# AD_3.net
KiCad netlist of a schematic drawn in Altium Designer
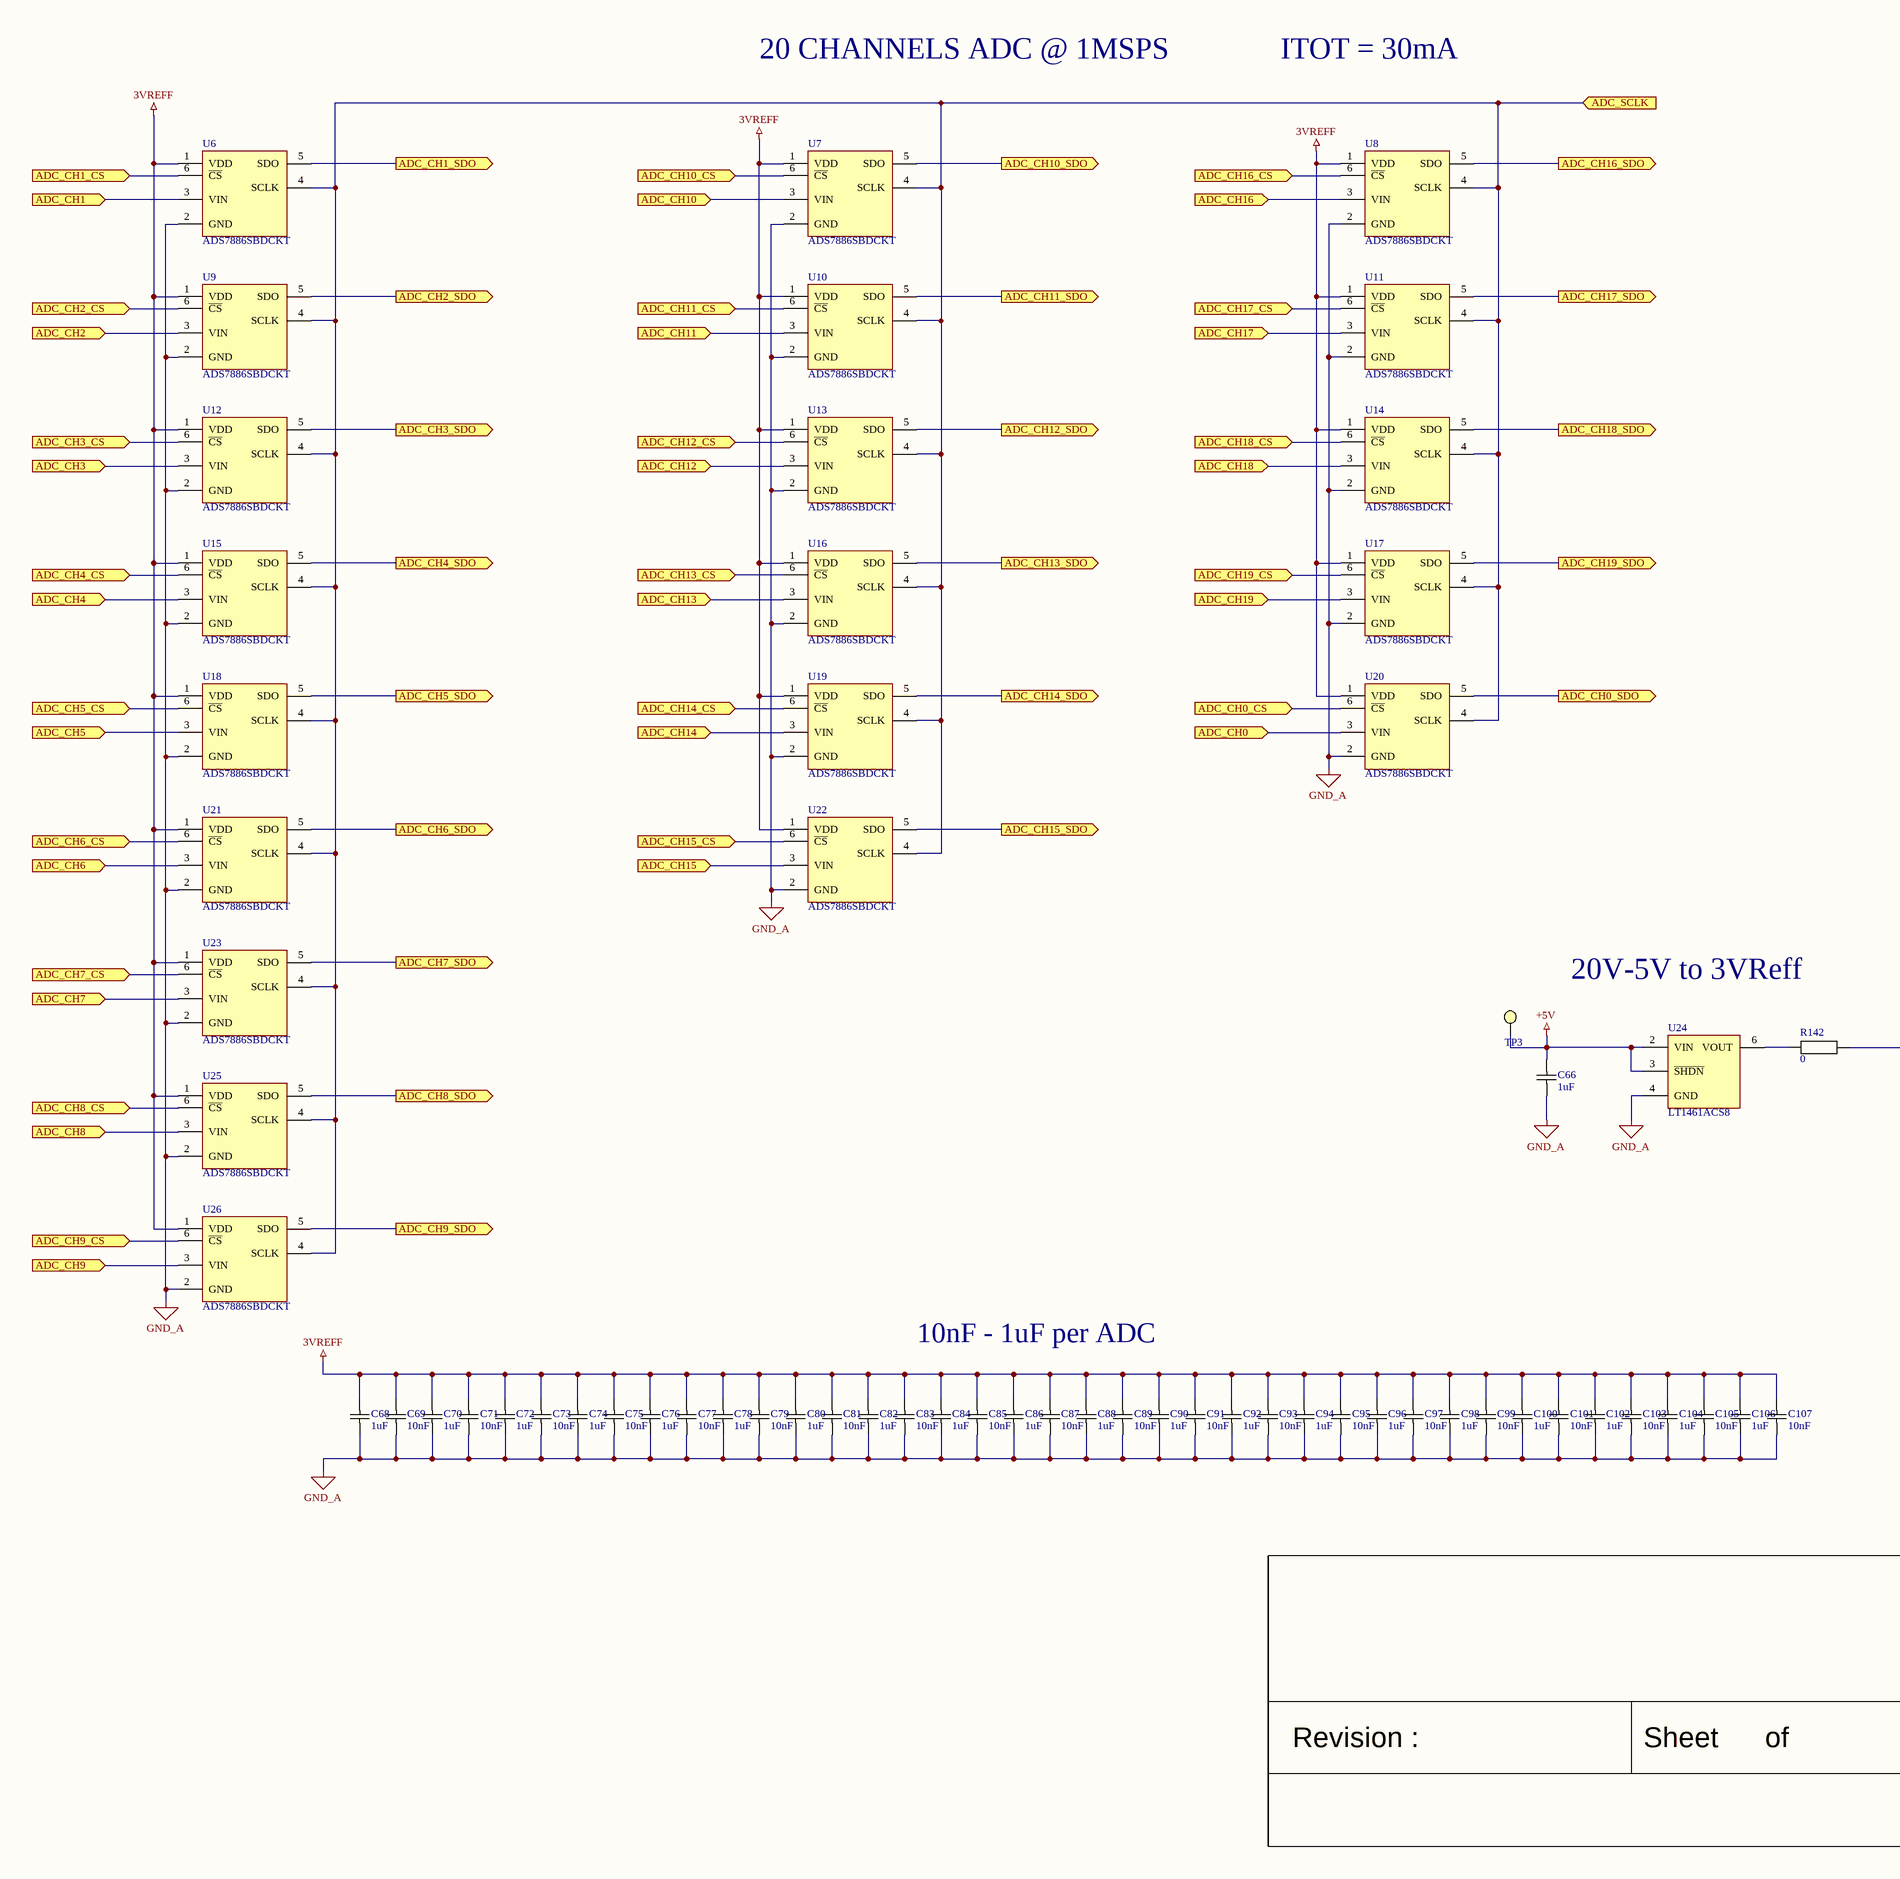
[diagram p0: AD_3.SchDoc, left]
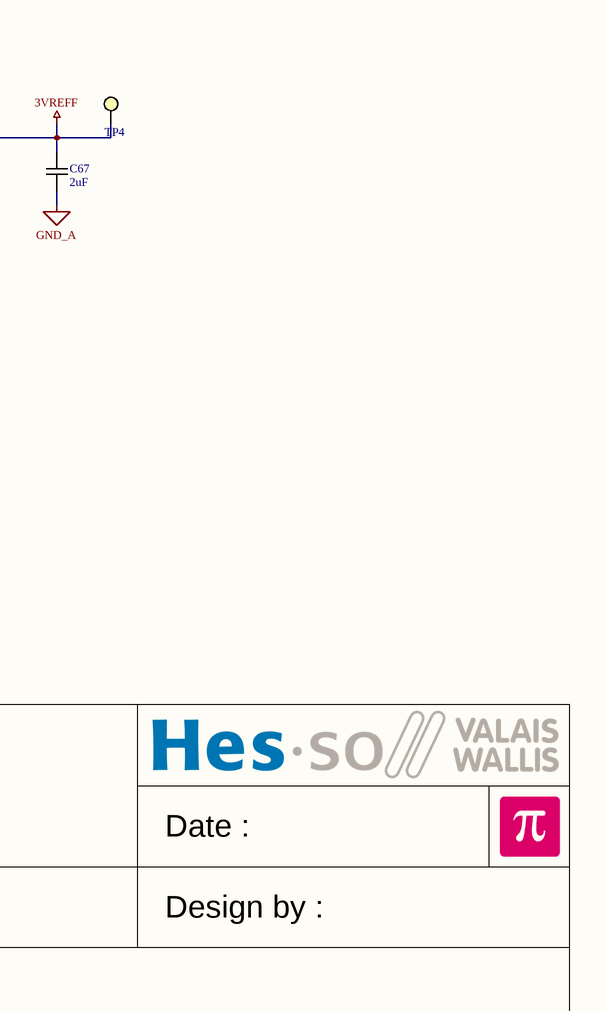
[diagram p1: AD_3.SchDoc, right]

(export (version "E")
  (design (tool "Eeschema 10.0.6"))
  (components
    (comp (ref "C66")
      (value "1uF")
      (footprint "CAPACITOR 1608 REFLOW")
      (description "Capacitor")
      (libsource (lib "Capacitor") (part "Capacitor"))
    )
    (comp (ref "C67")
      (value "2uF")
      (footprint "CAPACITOR 1608 REFLOW")
      (description "Capacitor")
      (libsource (lib "Capacitor") (part "Capacitor"))
    )
    (comp (ref "C68")
      (value "1uF")
      (footprint "CAPACITOR 1608 REFLOW")
      (description "Capacitor")
      (libsource (lib "Capacitor") (part "Capacitor"))
    )
    (comp (ref "C69")
      (value "10nF")
      (footprint "CAPACITOR 1608 REFLOW")
      (description "Capacitor")
      (libsource (lib "Capacitor") (part "Capacitor"))
    )
    (comp (ref "C70")
      (value "1uF")
      (footprint "CAPACITOR 1608 REFLOW")
      (description "Capacitor")
      (libsource (lib "Capacitor") (part "Capacitor"))
    )
    (comp (ref "C71")
      (value "10nF")
      (footprint "CAPACITOR 1608 REFLOW")
      (description "Capacitor")
      (libsource (lib "Capacitor") (part "Capacitor"))
    )
    (comp (ref "C72")
      (value "1uF")
      (footprint "CAPACITOR 1608 REFLOW")
      (description "Capacitor")
      (libsource (lib "Capacitor") (part "Capacitor"))
    )
    (comp (ref "C73")
      (value "10nF")
      (footprint "CAPACITOR 1608 REFLOW")
      (description "Capacitor")
      (libsource (lib "Capacitor") (part "Capacitor"))
    )
    (comp (ref "C74")
      (value "1uF")
      (footprint "CAPACITOR 1608 REFLOW")
      (description "Capacitor")
      (libsource (lib "Capacitor") (part "Capacitor"))
    )
    (comp (ref "C75")
      (value "10nF")
      (footprint "CAPACITOR 1608 REFLOW")
      (description "Capacitor")
      (libsource (lib "Capacitor") (part "Capacitor"))
    )
    (comp (ref "C76")
      (value "1uF")
      (footprint "CAPACITOR 1608 REFLOW")
      (description "Capacitor")
      (libsource (lib "Capacitor") (part "Capacitor"))
    )
    (comp (ref "C77")
      (value "10nF")
      (footprint "CAPACITOR 1608 REFLOW")
      (description "Capacitor")
      (libsource (lib "Capacitor") (part "Capacitor"))
    )
    (comp (ref "C78")
      (value "1uF")
      (footprint "CAPACITOR 1608 REFLOW")
      (description "Capacitor")
      (libsource (lib "Capacitor") (part "Capacitor"))
    )
    (comp (ref "C79")
      (value "10nF")
      (footprint "CAPACITOR 1608 REFLOW")
      (description "Capacitor")
      (libsource (lib "Capacitor") (part "Capacitor"))
    )
    (comp (ref "C80")
      (value "1uF")
      (footprint "CAPACITOR 1608 REFLOW")
      (description "Capacitor")
      (libsource (lib "Capacitor") (part "Capacitor"))
    )
    (comp (ref "C81")
      (value "10nF")
      (footprint "CAPACITOR 1608 REFLOW")
      (description "Capacitor")
      (libsource (lib "Capacitor") (part "Capacitor"))
    )
    (comp (ref "C82")
      (value "1uF")
      (footprint "CAPACITOR 1608 REFLOW")
      (description "Capacitor")
      (libsource (lib "Capacitor") (part "Capacitor"))
    )
    (comp (ref "C83")
      (value "10nF")
      (footprint "CAPACITOR 1608 REFLOW")
      (description "Capacitor")
      (libsource (lib "Capacitor") (part "Capacitor"))
    )
    (comp (ref "C84")
      (value "1uF")
      (footprint "CAPACITOR 1608 REFLOW")
      (description "Capacitor")
      (libsource (lib "Capacitor") (part "Capacitor"))
    )
    (comp (ref "C85")
      (value "10nF")
      (footprint "CAPACITOR 1608 REFLOW")
      (description "Capacitor")
      (libsource (lib "Capacitor") (part "Capacitor"))
    )
    (comp (ref "C86")
      (value "1uF")
      (footprint "CAPACITOR 1608 REFLOW")
      (description "Capacitor")
      (libsource (lib "Capacitor") (part "Capacitor"))
    )
    (comp (ref "C87")
      (value "10nF")
      (footprint "CAPACITOR 1608 REFLOW")
      (description "Capacitor")
      (libsource (lib "Capacitor") (part "Capacitor"))
    )
    (comp (ref "C88")
      (value "1uF")
      (footprint "CAPACITOR 1608 REFLOW")
      (description "Capacitor")
      (libsource (lib "Capacitor") (part "Capacitor"))
    )
    (comp (ref "C89")
      (value "10nF")
      (footprint "CAPACITOR 1608 REFLOW")
      (description "Capacitor")
      (libsource (lib "Capacitor") (part "Capacitor"))
    )
    (comp (ref "C90")
      (value "1uF")
      (footprint "CAPACITOR 1608 REFLOW")
      (description "Capacitor")
      (libsource (lib "Capacitor") (part "Capacitor"))
    )
    (comp (ref "C91")
      (value "10nF")
      (footprint "CAPACITOR 1608 REFLOW")
      (description "Capacitor")
      (libsource (lib "Capacitor") (part "Capacitor"))
    )
    (comp (ref "C92")
      (value "1uF")
      (footprint "CAPACITOR 1608 REFLOW")
      (description "Capacitor")
      (libsource (lib "Capacitor") (part "Capacitor"))
    )
    (comp (ref "C93")
      (value "10nF")
      (footprint "CAPACITOR 1608 REFLOW")
      (description "Capacitor")
      (libsource (lib "Capacitor") (part "Capacitor"))
    )
    (comp (ref "C94")
      (value "1uF")
      (footprint "CAPACITOR 1608 REFLOW")
      (description "Capacitor")
      (libsource (lib "Capacitor") (part "Capacitor"))
    )
    (comp (ref "C95")
      (value "10nF")
      (footprint "CAPACITOR 1608 REFLOW")
      (description "Capacitor")
      (libsource (lib "Capacitor") (part "Capacitor"))
    )
    (comp (ref "C96")
      (value "1uF")
      (footprint "CAPACITOR 1608 REFLOW")
      (description "Capacitor")
      (libsource (lib "Capacitor") (part "Capacitor"))
    )
    (comp (ref "C97")
      (value "10nF")
      (footprint "CAPACITOR 1608 REFLOW")
      (description "Capacitor")
      (libsource (lib "Capacitor") (part "Capacitor"))
    )
    (comp (ref "C98")
      (value "1uF")
      (footprint "CAPACITOR 1608 REFLOW")
      (description "Capacitor")
      (libsource (lib "Capacitor") (part "Capacitor"))
    )
    (comp (ref "C99")
      (value "10nF")
      (footprint "CAPACITOR 1608 REFLOW")
      (description "Capacitor")
      (libsource (lib "Capacitor") (part "Capacitor"))
    )
    (comp (ref "C100")
      (value "1uF")
      (footprint "CAPACITOR 1608 REFLOW")
      (description "Capacitor")
      (libsource (lib "Capacitor") (part "Capacitor"))
    )
    (comp (ref "C101")
      (value "10nF")
      (footprint "CAPACITOR 1608 REFLOW")
      (description "Capacitor")
      (libsource (lib "Capacitor") (part "Capacitor"))
    )
    (comp (ref "C102")
      (value "1uF")
      (footprint "CAPACITOR 1608 REFLOW")
      (description "Capacitor")
      (libsource (lib "Capacitor") (part "Capacitor"))
    )
    (comp (ref "C103")
      (value "10nF")
      (footprint "CAPACITOR 1608 REFLOW")
      (description "Capacitor")
      (libsource (lib "Capacitor") (part "Capacitor"))
    )
    (comp (ref "C104")
      (value "1uF")
      (footprint "CAPACITOR 1608 REFLOW")
      (description "Capacitor")
      (libsource (lib "Capacitor") (part "Capacitor"))
    )
    (comp (ref "C105")
      (value "10nF")
      (footprint "CAPACITOR 1608 REFLOW")
      (description "Capacitor")
      (libsource (lib "Capacitor") (part "Capacitor"))
    )
    (comp (ref "C106")
      (value "1uF")
      (footprint "CAPACITOR 1608 REFLOW")
      (description "Capacitor")
      (libsource (lib "Capacitor") (part "Capacitor"))
    )
    (comp (ref "C107")
      (value "10nF")
      (footprint "CAPACITOR 1608 REFLOW")
      (description "Capacitor")
      (libsource (lib "Capacitor") (part "Capacitor"))
    )
    (comp (ref "R142")
      (value "0")
      (footprint "RESISTOR 1608 REFLOW")
      (description "Resistor 1% 50V 100mW 1608(0603)")
      (libsource (lib "Resistor") (part "Resistor"))
    )
    (comp (ref "TP3")
      (value "*")
      (footprint "Test Point Keystone Miniature RED")
      (description "Test Point")
      (libsource (lib "Testpoint") (part "Test Point"))
    )
    (comp (ref "TP4")
      (value "*")
      (footprint "Test Point Keystone Miniature RED")
      (description "Test Point")
      (libsource (lib "Testpoint") (part "Test Point"))
    )
    (comp (ref "U6")
      (value "ADS7886SBDCKT")
      (footprint "SOT23-6 P0.95 C1.5x3.0 H1.3")
      (description "12-Bit, 1-MSPS, Micro-Power, Miniature SAR Analog-to-Digital Converters")
      (libsource (lib "Converter") (part "ADS7886SBDCKT"))
    )
    (comp (ref "U7")
      (value "ADS7886SBDCKT")
      (footprint "SOT23-6 P0.95 C1.5x3.0 H1.3")
      (description "12-Bit, 1-MSPS, Micro-Power, Miniature SAR Analog-to-Digital Converters")
      (libsource (lib "Converter") (part "ADS7886SBDCKT"))
    )
    (comp (ref "U8")
      (value "ADS7886SBDCKT")
      (footprint "SOT23-6 P0.95 C1.5x3.0 H1.3")
      (description "12-Bit, 1-MSPS, Micro-Power, Miniature SAR Analog-to-Digital Converters")
      (libsource (lib "Converter") (part "ADS7886SBDCKT"))
    )
    (comp (ref "U9")
      (value "ADS7886SBDCKT")
      (footprint "SOT23-6 P0.95 C1.5x3.0 H1.3")
      (description "12-Bit, 1-MSPS, Micro-Power, Miniature SAR Analog-to-Digital Converters")
      (libsource (lib "Converter") (part "ADS7886SBDCKT"))
    )
    (comp (ref "U10")
      (value "ADS7886SBDCKT")
      (footprint "SOT23-6 P0.95 C1.5x3.0 H1.3")
      (description "12-Bit, 1-MSPS, Micro-Power, Miniature SAR Analog-to-Digital Converters")
      (libsource (lib "Converter") (part "ADS7886SBDCKT"))
    )
    (comp (ref "U11")
      (value "ADS7886SBDCKT")
      (footprint "SOT23-6 P0.95 C1.5x3.0 H1.3")
      (description "12-Bit, 1-MSPS, Micro-Power, Miniature SAR Analog-to-Digital Converters")
      (libsource (lib "Converter") (part "ADS7886SBDCKT"))
    )
    (comp (ref "U12")
      (value "ADS7886SBDCKT")
      (footprint "SOT23-6 P0.95 C1.5x3.0 H1.3")
      (description "12-Bit, 1-MSPS, Micro-Power, Miniature SAR Analog-to-Digital Converters")
      (libsource (lib "Converter") (part "ADS7886SBDCKT"))
    )
    (comp (ref "U13")
      (value "ADS7886SBDCKT")
      (footprint "SOT23-6 P0.95 C1.5x3.0 H1.3")
      (description "12-Bit, 1-MSPS, Micro-Power, Miniature SAR Analog-to-Digital Converters")
      (libsource (lib "Converter") (part "ADS7886SBDCKT"))
    )
    (comp (ref "U14")
      (value "ADS7886SBDCKT")
      (footprint "SOT23-6 P0.95 C1.5x3.0 H1.3")
      (description "12-Bit, 1-MSPS, Micro-Power, Miniature SAR Analog-to-Digital Converters")
      (libsource (lib "Converter") (part "ADS7886SBDCKT"))
    )
    (comp (ref "U15")
      (value "ADS7886SBDCKT")
      (footprint "SOT23-6 P0.95 C1.5x3.0 H1.3")
      (description "12-Bit, 1-MSPS, Micro-Power, Miniature SAR Analog-to-Digital Converters")
      (libsource (lib "Converter") (part "ADS7886SBDCKT"))
    )
    (comp (ref "U16")
      (value "ADS7886SBDCKT")
      (footprint "SOT23-6 P0.95 C1.5x3.0 H1.3")
      (description "12-Bit, 1-MSPS, Micro-Power, Miniature SAR Analog-to-Digital Converters")
      (libsource (lib "Converter") (part "ADS7886SBDCKT"))
    )
    (comp (ref "U17")
      (value "ADS7886SBDCKT")
      (footprint "SOT23-6 P0.95 C1.5x3.0 H1.3")
      (description "12-Bit, 1-MSPS, Micro-Power, Miniature SAR Analog-to-Digital Converters")
      (libsource (lib "Converter") (part "ADS7886SBDCKT"))
    )
    (comp (ref "U18")
      (value "ADS7886SBDCKT")
      (footprint "SOT23-6 P0.95 C1.5x3.0 H1.3")
      (description "12-Bit, 1-MSPS, Micro-Power, Miniature SAR Analog-to-Digital Converters")
      (libsource (lib "Converter") (part "ADS7886SBDCKT"))
    )
    (comp (ref "U19")
      (value "ADS7886SBDCKT")
      (footprint "SOT23-6 P0.95 C1.5x3.0 H1.3")
      (description "12-Bit, 1-MSPS, Micro-Power, Miniature SAR Analog-to-Digital Converters")
      (libsource (lib "Converter") (part "ADS7886SBDCKT"))
    )
    (comp (ref "U20")
      (value "ADS7886SBDCKT")
      (footprint "SOT23-6 P0.95 C1.5x3.0 H1.3")
      (description "12-Bit, 1-MSPS, Micro-Power, Miniature SAR Analog-to-Digital Converters")
      (libsource (lib "Converter") (part "ADS7886SBDCKT"))
    )
    (comp (ref "U21")
      (value "ADS7886SBDCKT")
      (footprint "SOT23-6 P0.95 C1.5x3.0 H1.3")
      (description "12-Bit, 1-MSPS, Micro-Power, Miniature SAR Analog-to-Digital Converters")
      (libsource (lib "Converter") (part "ADS7886SBDCKT"))
    )
    (comp (ref "U22")
      (value "ADS7886SBDCKT")
      (footprint "SOT23-6 P0.95 C1.5x3.0 H1.3")
      (description "12-Bit, 1-MSPS, Micro-Power, Miniature SAR Analog-to-Digital Converters")
      (libsource (lib "Converter") (part "ADS7886SBDCKT"))
    )
    (comp (ref "U23")
      (value "ADS7886SBDCKT")
      (footprint "SOT23-6 P0.95 C1.5x3.0 H1.3")
      (description "12-Bit, 1-MSPS, Micro-Power, Miniature SAR Analog-to-Digital Converters")
      (libsource (lib "Converter") (part "ADS7886SBDCKT"))
    )
    (comp (ref "U24")
      (value "LT1461ACS8")
      (footprint "SO8 P1.27 C4.0X5.0 H1.75")
      (description "Micropower Precision Low Dropout Series Voltage Reference Family")
      (libsource (lib "Regulator") (part "LT1461ACS8"))
    )
    (comp (ref "U25")
      (value "ADS7886SBDCKT")
      (footprint "SOT23-6 P0.95 C1.5x3.0 H1.3")
      (description "12-Bit, 1-MSPS, Micro-Power, Miniature SAR Analog-to-Digital Converters")
      (libsource (lib "Converter") (part "ADS7886SBDCKT"))
    )
    (comp (ref "U26")
      (value "ADS7886SBDCKT")
      (footprint "SOT23-6 P0.95 C1.5x3.0 H1.3")
      (description "12-Bit, 1-MSPS, Micro-Power, Miniature SAR Analog-to-Digital Converters")
      (libsource (lib "Converter") (part "ADS7886SBDCKT"))
    )
  )
  (nets
    (net (code "1") (name "+5V") (class "Default")
      (node (ref "C66") (pin "2") (pinfunction "2_2") (pintype "passive"))
      (node (ref "TP3") (pin "1") (pinfunction "1_1") (pintype "passive"))
      (node (ref "U24") (pin "2") (pinfunction "VIN_2") (pintype "passive"))
      (node (ref "U24") (pin "3") (pinfunction "~{SHDN}_3") (pintype "passive"))
    )
    (net (code "2") (name "/ADC_CH0") (class "Default")
      (node (ref "U20") (pin "3") (pinfunction "VIN_3") (pintype "passive"))
    )
    (net (code "3") (name "/ADC_CH0_CS") (class "Default")
      (node (ref "U20") (pin "6") (pinfunction "~{CS}_6") (pintype "passive"))
    )
    (net (code "4") (name "/ADC_CH0_SDO") (class "Default")
      (node (ref "U20") (pin "5") (pinfunction "SDO_5") (pintype "passive"))
    )
    (net (code "5") (name "/ADC_CH1") (class "Default")
      (node (ref "U6") (pin "3") (pinfunction "VIN_3") (pintype "passive"))
    )
    (net (code "6") (name "/ADC_CH1_CS") (class "Default")
      (node (ref "U6") (pin "6") (pinfunction "~{CS}_6") (pintype "passive"))
    )
    (net (code "7") (name "/ADC_CH1_SDO") (class "Default")
      (node (ref "U6") (pin "5") (pinfunction "SDO_5") (pintype "passive"))
    )
    (net (code "8") (name "/ADC_CH2") (class "Default")
      (node (ref "U9") (pin "3") (pinfunction "VIN_3") (pintype "passive"))
    )
    (net (code "9") (name "/ADC_CH2_CS") (class "Default")
      (node (ref "U9") (pin "6") (pinfunction "~{CS}_6") (pintype "passive"))
    )
    (net (code "10") (name "/ADC_CH2_SDO") (class "Default")
      (node (ref "U9") (pin "5") (pinfunction "SDO_5") (pintype "passive"))
    )
    (net (code "11") (name "/ADC_CH3") (class "Default")
      (node (ref "U12") (pin "3") (pinfunction "VIN_3") (pintype "passive"))
    )
    (net (code "12") (name "/ADC_CH3_CS") (class "Default")
      (node (ref "U12") (pin "6") (pinfunction "~{CS}_6") (pintype "passive"))
    )
    (net (code "13") (name "/ADC_CH3_SDO") (class "Default")
      (node (ref "U12") (pin "5") (pinfunction "SDO_5") (pintype "passive"))
    )
    (net (code "14") (name "/ADC_CH4") (class "Default")
      (node (ref "U15") (pin "3") (pinfunction "VIN_3") (pintype "passive"))
    )
    (net (code "15") (name "/ADC_CH4_CS") (class "Default")
      (node (ref "U15") (pin "6") (pinfunction "~{CS}_6") (pintype "passive"))
    )
    (net (code "16") (name "/ADC_CH4_SDO") (class "Default")
      (node (ref "U15") (pin "5") (pinfunction "SDO_5") (pintype "passive"))
    )
    (net (code "17") (name "/ADC_CH5") (class "Default")
      (node (ref "U18") (pin "3") (pinfunction "VIN_3") (pintype "passive"))
    )
    (net (code "18") (name "/ADC_CH5_CS") (class "Default")
      (node (ref "U18") (pin "6") (pinfunction "~{CS}_6") (pintype "passive"))
    )
    (net (code "19") (name "/ADC_CH5_SDO") (class "Default")
      (node (ref "U18") (pin "5") (pinfunction "SDO_5") (pintype "passive"))
    )
    (net (code "20") (name "/ADC_CH6") (class "Default")
      (node (ref "U21") (pin "3") (pinfunction "VIN_3") (pintype "passive"))
    )
    (net (code "21") (name "/ADC_CH6_CS") (class "Default")
      (node (ref "U21") (pin "6") (pinfunction "~{CS}_6") (pintype "passive"))
    )
    (net (code "22") (name "/ADC_CH6_SDO") (class "Default")
      (node (ref "U21") (pin "5") (pinfunction "SDO_5") (pintype "passive"))
    )
    (net (code "23") (name "/ADC_CH7") (class "Default")
      (node (ref "U23") (pin "3") (pinfunction "VIN_3") (pintype "passive"))
    )
    (net (code "24") (name "/ADC_CH7_CS") (class "Default")
      (node (ref "U23") (pin "6") (pinfunction "~{CS}_6") (pintype "passive"))
    )
    (net (code "25") (name "/ADC_CH7_SDO") (class "Default")
      (node (ref "U23") (pin "5") (pinfunction "SDO_5") (pintype "passive"))
    )
    (net (code "26") (name "/ADC_CH8") (class "Default")
      (node (ref "U25") (pin "3") (pinfunction "VIN_3") (pintype "passive"))
    )
    (net (code "27") (name "/ADC_CH8_CS") (class "Default")
      (node (ref "U25") (pin "6") (pinfunction "~{CS}_6") (pintype "passive"))
    )
    (net (code "28") (name "/ADC_CH8_SDO") (class "Default")
      (node (ref "U25") (pin "5") (pinfunction "SDO_5") (pintype "passive"))
    )
    (net (code "29") (name "/ADC_CH9") (class "Default")
      (node (ref "U26") (pin "3") (pinfunction "VIN_3") (pintype "passive"))
    )
    (net (code "30") (name "/ADC_CH9_CS") (class "Default")
      (node (ref "U26") (pin "6") (pinfunction "~{CS}_6") (pintype "passive"))
    )
    (net (code "31") (name "/ADC_CH9_SDO") (class "Default")
      (node (ref "U26") (pin "5") (pinfunction "SDO_5") (pintype "passive"))
    )
    (net (code "32") (name "/ADC_CH10") (class "Default")
      (node (ref "U7") (pin "3") (pinfunction "VIN_3") (pintype "passive"))
    )
    (net (code "33") (name "/ADC_CH10_CS") (class "Default")
      (node (ref "U7") (pin "6") (pinfunction "~{CS}_6") (pintype "passive"))
    )
    (net (code "34") (name "/ADC_CH10_SDO") (class "Default")
      (node (ref "U7") (pin "5") (pinfunction "SDO_5") (pintype "passive"))
    )
    (net (code "35") (name "/ADC_CH11") (class "Default")
      (node (ref "U10") (pin "3") (pinfunction "VIN_3") (pintype "passive"))
    )
    (net (code "36") (name "/ADC_CH11_CS") (class "Default")
      (node (ref "U10") (pin "6") (pinfunction "~{CS}_6") (pintype "passive"))
    )
    (net (code "37") (name "/ADC_CH11_SDO") (class "Default")
      (node (ref "U10") (pin "5") (pinfunction "SDO_5") (pintype "passive"))
    )
    (net (code "38") (name "/ADC_CH12") (class "Default")
      (node (ref "U13") (pin "3") (pinfunction "VIN_3") (pintype "passive"))
    )
    (net (code "39") (name "/ADC_CH12_CS") (class "Default")
      (node (ref "U13") (pin "6") (pinfunction "~{CS}_6") (pintype "passive"))
    )
    (net (code "40") (name "/ADC_CH12_SDO") (class "Default")
      (node (ref "U13") (pin "5") (pinfunction "SDO_5") (pintype "passive"))
    )
    (net (code "41") (name "/ADC_CH13") (class "Default")
      (node (ref "U16") (pin "3") (pinfunction "VIN_3") (pintype "passive"))
    )
    (net (code "42") (name "/ADC_CH13_CS") (class "Default")
      (node (ref "U16") (pin "6") (pinfunction "~{CS}_6") (pintype "passive"))
    )
    (net (code "43") (name "/ADC_CH13_SDO") (class "Default")
      (node (ref "U16") (pin "5") (pinfunction "SDO_5") (pintype "passive"))
    )
    (net (code "44") (name "/ADC_CH14") (class "Default")
      (node (ref "U19") (pin "3") (pinfunction "VIN_3") (pintype "passive"))
    )
    (net (code "45") (name "/ADC_CH14_CS") (class "Default")
      (node (ref "U19") (pin "6") (pinfunction "~{CS}_6") (pintype "passive"))
    )
    (net (code "46") (name "/ADC_CH14_SDO") (class "Default")
      (node (ref "U19") (pin "5") (pinfunction "SDO_5") (pintype "passive"))
    )
    (net (code "47") (name "/ADC_CH15") (class "Default")
      (node (ref "U22") (pin "3") (pinfunction "VIN_3") (pintype "passive"))
    )
    (net (code "48") (name "/ADC_CH15_CS") (class "Default")
      (node (ref "U22") (pin "6") (pinfunction "~{CS}_6") (pintype "passive"))
    )
    (net (code "49") (name "/ADC_CH15_SDO") (class "Default")
      (node (ref "U22") (pin "5") (pinfunction "SDO_5") (pintype "passive"))
    )
    (net (code "50") (name "/ADC_CH16") (class "Default")
      (node (ref "U8") (pin "3") (pinfunction "VIN_3") (pintype "passive"))
    )
    (net (code "51") (name "/ADC_CH16_CS") (class "Default")
      (node (ref "U8") (pin "6") (pinfunction "~{CS}_6") (pintype "passive"))
    )
    (net (code "52") (name "/ADC_CH16_SDO") (class "Default")
      (node (ref "U8") (pin "5") (pinfunction "SDO_5") (pintype "passive"))
    )
    (net (code "53") (name "/ADC_CH17") (class "Default")
      (node (ref "U11") (pin "3") (pinfunction "VIN_3") (pintype "passive"))
    )
    (net (code "54") (name "/ADC_CH17_CS") (class "Default")
      (node (ref "U11") (pin "6") (pinfunction "~{CS}_6") (pintype "passive"))
    )
    (net (code "55") (name "/ADC_CH17_SDO") (class "Default")
      (node (ref "U11") (pin "5") (pinfunction "SDO_5") (pintype "passive"))
    )
    (net (code "56") (name "/ADC_CH18") (class "Default")
      (node (ref "U14") (pin "3") (pinfunction "VIN_3") (pintype "passive"))
    )
    (net (code "57") (name "/ADC_CH18_CS") (class "Default")
      (node (ref "U14") (pin "6") (pinfunction "~{CS}_6") (pintype "passive"))
    )
    (net (code "58") (name "/ADC_CH18_SDO") (class "Default")
      (node (ref "U14") (pin "5") (pinfunction "SDO_5") (pintype "passive"))
    )
    (net (code "59") (name "/ADC_CH19") (class "Default")
      (node (ref "U17") (pin "3") (pinfunction "VIN_3") (pintype "passive"))
    )
    (net (code "60") (name "/ADC_CH19_CS") (class "Default")
      (node (ref "U17") (pin "6") (pinfunction "~{CS}_6") (pintype "passive"))
    )
    (net (code "61") (name "/ADC_CH19_SDO") (class "Default")
      (node (ref "U17") (pin "5") (pinfunction "SDO_5") (pintype "passive"))
    )
    (net (code "62") (name "/ADC_SCLK") (class "Default")
      (node (ref "U10") (pin "4") (pinfunction "SCLK_4") (pintype "passive"))
      (node (ref "U11") (pin "4") (pinfunction "SCLK_4") (pintype "passive"))
      (node (ref "U12") (pin "4") (pinfunction "SCLK_4") (pintype "passive"))
      (node (ref "U13") (pin "4") (pinfunction "SCLK_4") (pintype "passive"))
      (node (ref "U14") (pin "4") (pinfunction "SCLK_4") (pintype "passive"))
      (node (ref "U15") (pin "4") (pinfunction "SCLK_4") (pintype "passive"))
      (node (ref "U16") (pin "4") (pinfunction "SCLK_4") (pintype "passive"))
      (node (ref "U17") (pin "4") (pinfunction "SCLK_4") (pintype "passive"))
      (node (ref "U18") (pin "4") (pinfunction "SCLK_4") (pintype "passive"))
      (node (ref "U19") (pin "4") (pinfunction "SCLK_4") (pintype "passive"))
      (node (ref "U20") (pin "4") (pinfunction "SCLK_4") (pintype "passive"))
      (node (ref "U21") (pin "4") (pinfunction "SCLK_4") (pintype "passive"))
      (node (ref "U22") (pin "4") (pinfunction "SCLK_4") (pintype "passive"))
      (node (ref "U23") (pin "4") (pinfunction "SCLK_4") (pintype "passive"))
      (node (ref "U25") (pin "4") (pinfunction "SCLK_4") (pintype "passive"))
      (node (ref "U26") (pin "4") (pinfunction "SCLK_4") (pintype "passive"))
      (node (ref "U6") (pin "4") (pinfunction "SCLK_4") (pintype "passive"))
      (node (ref "U7") (pin "4") (pinfunction "SCLK_4") (pintype "passive"))
      (node (ref "U8") (pin "4") (pinfunction "SCLK_4") (pintype "passive"))
      (node (ref "U9") (pin "4") (pinfunction "SCLK_4") (pintype "passive"))
    )
    (net (code "63") (name "3VREFF") (class "Default")
      (node (ref "C100") (pin "2") (pinfunction "2_2") (pintype "passive"))
      (node (ref "C101") (pin "2") (pinfunction "2_2") (pintype "passive"))
      (node (ref "C102") (pin "2") (pinfunction "2_2") (pintype "passive"))
      (node (ref "C103") (pin "2") (pinfunction "2_2") (pintype "passive"))
      (node (ref "C104") (pin "2") (pinfunction "2_2") (pintype "passive"))
      (node (ref "C105") (pin "2") (pinfunction "2_2") (pintype "passive"))
      (node (ref "C106") (pin "2") (pinfunction "2_2") (pintype "passive"))
      (node (ref "C107") (pin "2") (pinfunction "2_2") (pintype "passive"))
      (node (ref "C67") (pin "2") (pinfunction "2_2") (pintype "passive"))
      (node (ref "C68") (pin "2") (pinfunction "2_2") (pintype "passive"))
      (node (ref "C69") (pin "2") (pinfunction "2_2") (pintype "passive"))
      (node (ref "C70") (pin "2") (pinfunction "2_2") (pintype "passive"))
      (node (ref "C71") (pin "2") (pinfunction "2_2") (pintype "passive"))
      (node (ref "C72") (pin "2") (pinfunction "2_2") (pintype "passive"))
      (node (ref "C73") (pin "2") (pinfunction "2_2") (pintype "passive"))
      (node (ref "C74") (pin "2") (pinfunction "2_2") (pintype "passive"))
      (node (ref "C75") (pin "2") (pinfunction "2_2") (pintype "passive"))
      (node (ref "C76") (pin "2") (pinfunction "2_2") (pintype "passive"))
      (node (ref "C77") (pin "2") (pinfunction "2_2") (pintype "passive"))
      (node (ref "C78") (pin "2") (pinfunction "2_2") (pintype "passive"))
      (node (ref "C79") (pin "2") (pinfunction "2_2") (pintype "passive"))
      (node (ref "C80") (pin "2") (pinfunction "2_2") (pintype "passive"))
      (node (ref "C81") (pin "2") (pinfunction "2_2") (pintype "passive"))
      (node (ref "C82") (pin "2") (pinfunction "2_2") (pintype "passive"))
      (node (ref "C83") (pin "2") (pinfunction "2_2") (pintype "passive"))
      (node (ref "C84") (pin "2") (pinfunction "2_2") (pintype "passive"))
      (node (ref "C85") (pin "2") (pinfunction "2_2") (pintype "passive"))
      (node (ref "C86") (pin "2") (pinfunction "2_2") (pintype "passive"))
      (node (ref "C87") (pin "2") (pinfunction "2_2") (pintype "passive"))
      (node (ref "C88") (pin "2") (pinfunction "2_2") (pintype "passive"))
      (node (ref "C89") (pin "2") (pinfunction "2_2") (pintype "passive"))
      (node (ref "C90") (pin "2") (pinfunction "2_2") (pintype "passive"))
      (node (ref "C91") (pin "2") (pinfunction "2_2") (pintype "passive"))
      (node (ref "C92") (pin "2") (pinfunction "2_2") (pintype "passive"))
      (node (ref "C93") (pin "2") (pinfunction "2_2") (pintype "passive"))
      (node (ref "C94") (pin "2") (pinfunction "2_2") (pintype "passive"))
      (node (ref "C95") (pin "2") (pinfunction "2_2") (pintype "passive"))
      (node (ref "C96") (pin "2") (pinfunction "2_2") (pintype "passive"))
      (node (ref "C97") (pin "2") (pinfunction "2_2") (pintype "passive"))
      (node (ref "C98") (pin "2") (pinfunction "2_2") (pintype "passive"))
      (node (ref "C99") (pin "2") (pinfunction "2_2") (pintype "passive"))
      (node (ref "R142") (pin "2") (pinfunction "2_2") (pintype "passive"))
      (node (ref "TP4") (pin "1") (pinfunction "1_1") (pintype "passive"))
      (node (ref "U10") (pin "1") (pinfunction "VDD_1") (pintype "passive"))
      (node (ref "U11") (pin "1") (pinfunction "VDD_1") (pintype "passive"))
      (node (ref "U12") (pin "1") (pinfunction "VDD_1") (pintype "passive"))
      (node (ref "U13") (pin "1") (pinfunction "VDD_1") (pintype "passive"))
      (node (ref "U14") (pin "1") (pinfunction "VDD_1") (pintype "passive"))
      (node (ref "U15") (pin "1") (pinfunction "VDD_1") (pintype "passive"))
      (node (ref "U16") (pin "1") (pinfunction "VDD_1") (pintype "passive"))
      (node (ref "U17") (pin "1") (pinfunction "VDD_1") (pintype "passive"))
      (node (ref "U18") (pin "1") (pinfunction "VDD_1") (pintype "passive"))
      (node (ref "U19") (pin "1") (pinfunction "VDD_1") (pintype "passive"))
      (node (ref "U20") (pin "1") (pinfunction "VDD_1") (pintype "passive"))
      (node (ref "U21") (pin "1") (pinfunction "VDD_1") (pintype "passive"))
      (node (ref "U22") (pin "1") (pinfunction "VDD_1") (pintype "passive"))
      (node (ref "U23") (pin "1") (pinfunction "VDD_1") (pintype "passive"))
      (node (ref "U25") (pin "1") (pinfunction "VDD_1") (pintype "passive"))
      (node (ref "U26") (pin "1") (pinfunction "VDD_1") (pintype "passive"))
      (node (ref "U6") (pin "1") (pinfunction "VDD_1") (pintype "passive"))
      (node (ref "U7") (pin "1") (pinfunction "VDD_1") (pintype "passive"))
      (node (ref "U8") (pin "1") (pinfunction "VDD_1") (pintype "passive"))
      (node (ref "U9") (pin "1") (pinfunction "VDD_1") (pintype "passive"))
    )
    (net (code "64") (name "GND_A") (class "Default")
      (node (ref "C100") (pin "1") (pinfunction "1_1") (pintype "passive"))
      (node (ref "C101") (pin "1") (pinfunction "1_1") (pintype "passive"))
      (node (ref "C102") (pin "1") (pinfunction "1_1") (pintype "passive"))
      (node (ref "C103") (pin "1") (pinfunction "1_1") (pintype "passive"))
      (node (ref "C104") (pin "1") (pinfunction "1_1") (pintype "passive"))
      (node (ref "C105") (pin "1") (pinfunction "1_1") (pintype "passive"))
      (node (ref "C106") (pin "1") (pinfunction "1_1") (pintype "passive"))
      (node (ref "C107") (pin "1") (pinfunction "1_1") (pintype "passive"))
      (node (ref "C66") (pin "1") (pinfunction "1_1") (pintype "passive"))
      (node (ref "C67") (pin "1") (pinfunction "1_1") (pintype "passive"))
      (node (ref "C68") (pin "1") (pinfunction "1_1") (pintype "passive"))
      (node (ref "C69") (pin "1") (pinfunction "1_1") (pintype "passive"))
      (node (ref "C70") (pin "1") (pinfunction "1_1") (pintype "passive"))
      (node (ref "C71") (pin "1") (pinfunction "1_1") (pintype "passive"))
      (node (ref "C72") (pin "1") (pinfunction "1_1") (pintype "passive"))
      (node (ref "C73") (pin "1") (pinfunction "1_1") (pintype "passive"))
      (node (ref "C74") (pin "1") (pinfunction "1_1") (pintype "passive"))
      (node (ref "C75") (pin "1") (pinfunction "1_1") (pintype "passive"))
      (node (ref "C76") (pin "1") (pinfunction "1_1") (pintype "passive"))
      (node (ref "C77") (pin "1") (pinfunction "1_1") (pintype "passive"))
      (node (ref "C78") (pin "1") (pinfunction "1_1") (pintype "passive"))
      (node (ref "C79") (pin "1") (pinfunction "1_1") (pintype "passive"))
      (node (ref "C80") (pin "1") (pinfunction "1_1") (pintype "passive"))
      (node (ref "C81") (pin "1") (pinfunction "1_1") (pintype "passive"))
      (node (ref "C82") (pin "1") (pinfunction "1_1") (pintype "passive"))
      (node (ref "C83") (pin "1") (pinfunction "1_1") (pintype "passive"))
      (node (ref "C84") (pin "1") (pinfunction "1_1") (pintype "passive"))
      (node (ref "C85") (pin "1") (pinfunction "1_1") (pintype "passive"))
      (node (ref "C86") (pin "1") (pinfunction "1_1") (pintype "passive"))
      (node (ref "C87") (pin "1") (pinfunction "1_1") (pintype "passive"))
      (node (ref "C88") (pin "1") (pinfunction "1_1") (pintype "passive"))
      (node (ref "C89") (pin "1") (pinfunction "1_1") (pintype "passive"))
      (node (ref "C90") (pin "1") (pinfunction "1_1") (pintype "passive"))
      (node (ref "C91") (pin "1") (pinfunction "1_1") (pintype "passive"))
      (node (ref "C92") (pin "1") (pinfunction "1_1") (pintype "passive"))
      (node (ref "C93") (pin "1") (pinfunction "1_1") (pintype "passive"))
      (node (ref "C94") (pin "1") (pinfunction "1_1") (pintype "passive"))
      (node (ref "C95") (pin "1") (pinfunction "1_1") (pintype "passive"))
      (node (ref "C96") (pin "1") (pinfunction "1_1") (pintype "passive"))
      (node (ref "C97") (pin "1") (pinfunction "1_1") (pintype "passive"))
      (node (ref "C98") (pin "1") (pinfunction "1_1") (pintype "passive"))
      (node (ref "C99") (pin "1") (pinfunction "1_1") (pintype "passive"))
      (node (ref "U10") (pin "2") (pinfunction "GND_2") (pintype "passive"))
      (node (ref "U11") (pin "2") (pinfunction "GND_2") (pintype "passive"))
      (node (ref "U12") (pin "2") (pinfunction "GND_2") (pintype "passive"))
      (node (ref "U13") (pin "2") (pinfunction "GND_2") (pintype "passive"))
      (node (ref "U14") (pin "2") (pinfunction "GND_2") (pintype "passive"))
      (node (ref "U15") (pin "2") (pinfunction "GND_2") (pintype "passive"))
      (node (ref "U16") (pin "2") (pinfunction "GND_2") (pintype "passive"))
      (node (ref "U17") (pin "2") (pinfunction "GND_2") (pintype "passive"))
      (node (ref "U18") (pin "2") (pinfunction "GND_2") (pintype "passive"))
      (node (ref "U19") (pin "2") (pinfunction "GND_2") (pintype "passive"))
      (node (ref "U20") (pin "2") (pinfunction "GND_2") (pintype "passive"))
      (node (ref "U21") (pin "2") (pinfunction "GND_2") (pintype "passive"))
      (node (ref "U22") (pin "2") (pinfunction "GND_2") (pintype "passive"))
      (node (ref "U23") (pin "2") (pinfunction "GND_2") (pintype "passive"))
      (node (ref "U24") (pin "4") (pinfunction "GND_4") (pintype "passive"))
      (node (ref "U25") (pin "2") (pinfunction "GND_2") (pintype "passive"))
      (node (ref "U26") (pin "2") (pinfunction "GND_2") (pintype "passive"))
      (node (ref "U6") (pin "2") (pinfunction "GND_2") (pintype "passive"))
      (node (ref "U7") (pin "2") (pinfunction "GND_2") (pintype "passive"))
      (node (ref "U8") (pin "2") (pinfunction "GND_2") (pintype "passive"))
      (node (ref "U9") (pin "2") (pinfunction "GND_2") (pintype "passive"))
    )
    (net (code "65") (name "Net-(U24-VOUT)") (class "Default")
      (node (ref "R142") (pin "1") (pinfunction "1_1") (pintype "passive"))
      (node (ref "U24") (pin "6") (pinfunction "VOUT_6") (pintype "passive"))
    )
  )
)
